# motherboard.net
KiCad netlist of a schematic drawn in EAGLE
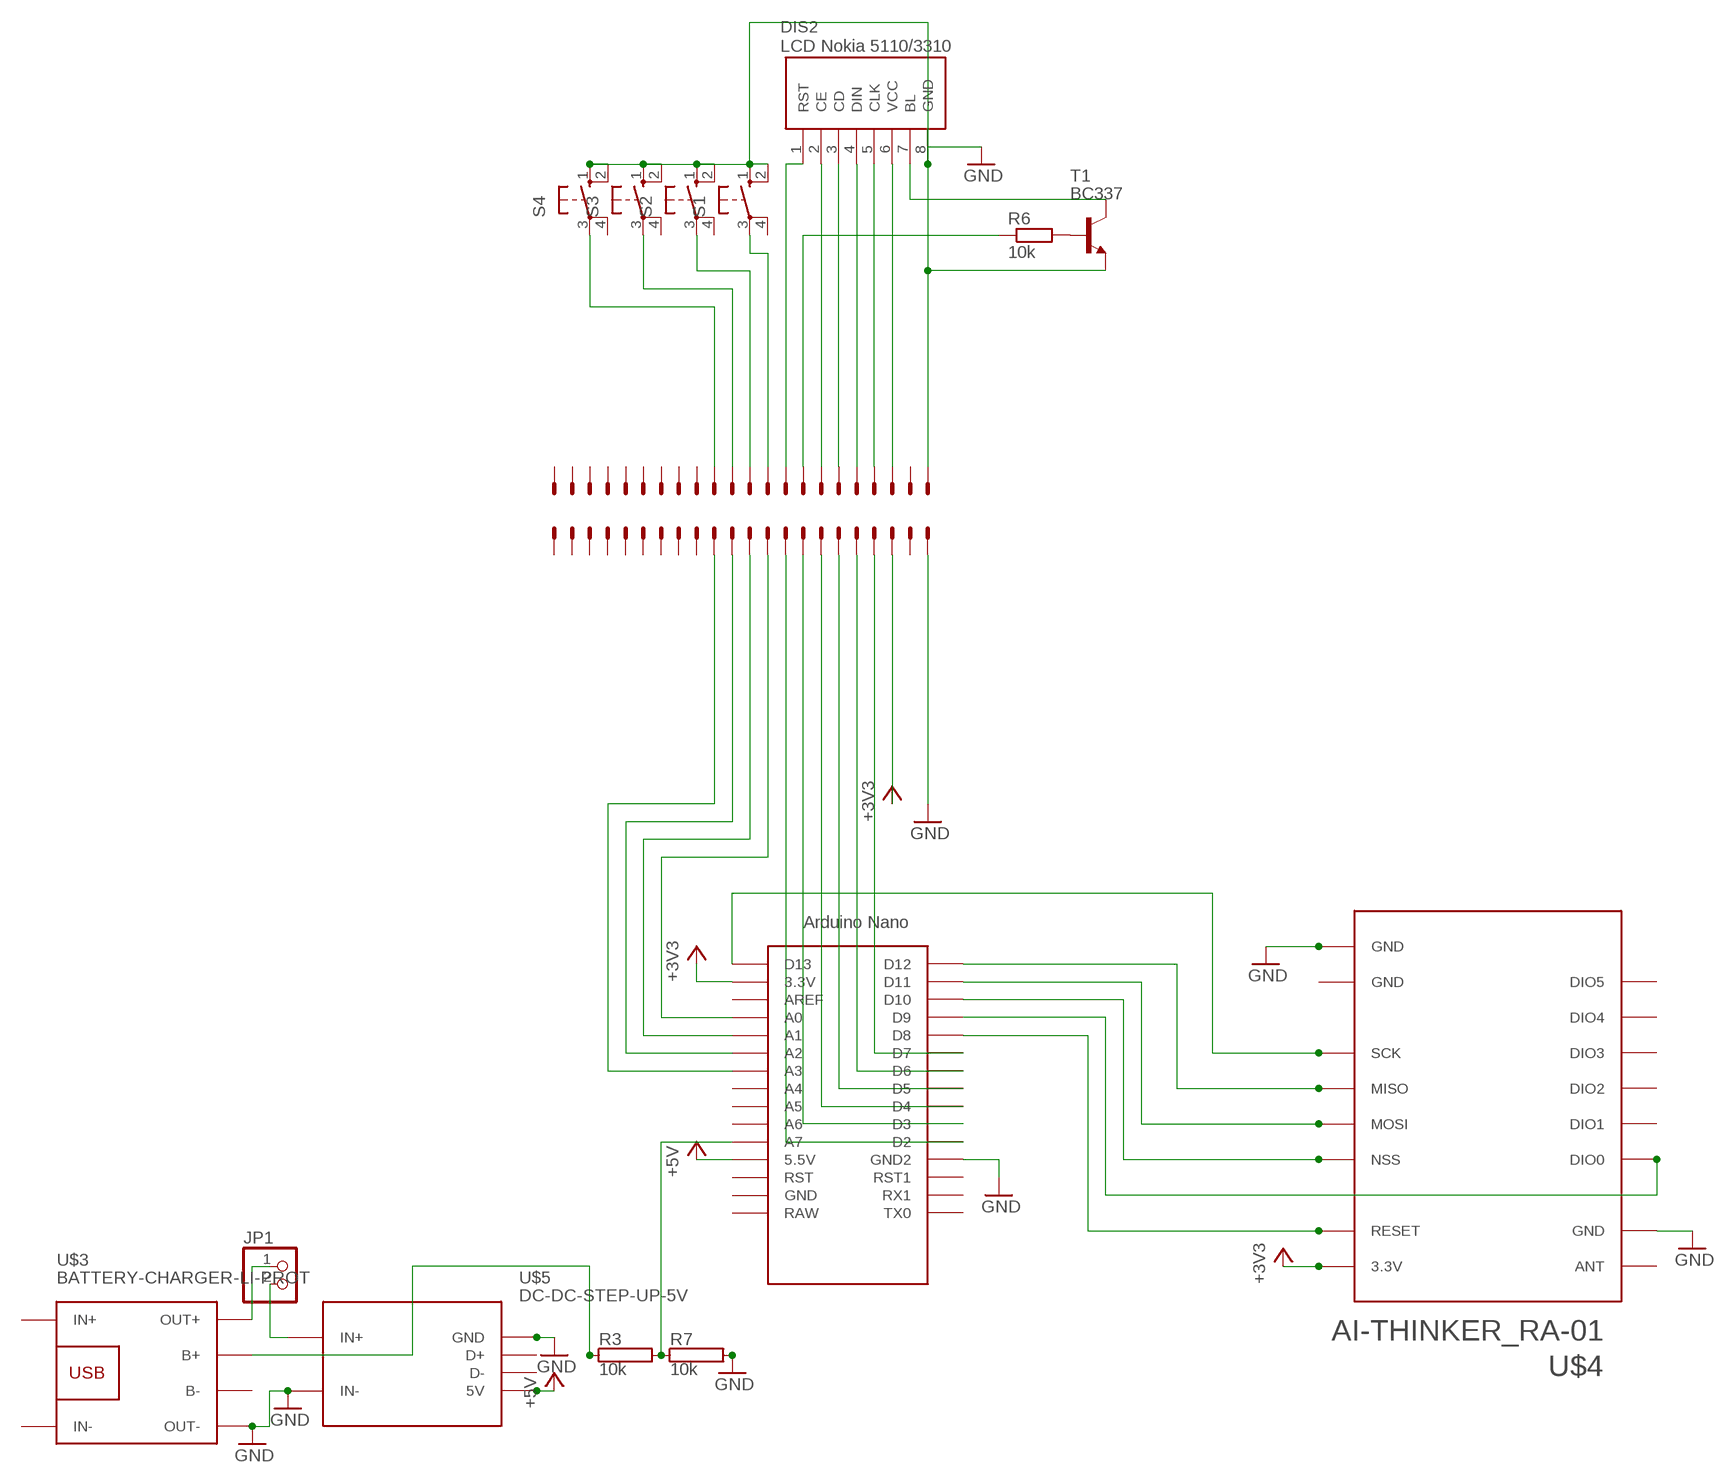
[diagram p0: schematic, sheet 1]

(export (version "E")
  (design (tool "Eeschema 10.0.6"))
  (components
    (comp (ref "DIS2")
      (value "NOKIA5110")
      (footprint "eagle-import:NOKIA5110")
      (libsource (lib "eagle-import") (part "NOKIA5110"))
    )
    (comp (ref "J1")
      (value "XF2L-2235-1")
      (footprint "eagle-import:XF2L-2235-1")
      (fields (field (name "MPN") "XF2L-2235-1A"))
      (libsource (lib "eagle-import") (part "XF2-22?35-1L"))
    )
    (comp (ref "J2")
      (value "XF2L-2235-1")
      (footprint "eagle-import:XF2L-2235-1")
      (fields (field (name "MPN") "XF2L-2235-1A"))
      (libsource (lib "eagle-import") (part "XF2-22?35-1L"))
    )
    (comp (ref "JP1")
      (value "PINHD-1X2/90")
      (footprint "eagle-import:1X02_90")
      (libsource (lib "eagle-import") (part "PINHD-1X2/90"))
    )
    (comp (ref "R3")
      (value "10k")
      (footprint "eagle-import:AC01")
      (libsource (lib "eagle-import") (part "RAC01"))
    )
    (comp (ref "R6")
      (value "10k")
      (footprint "eagle-import:0204_5")
      (libsource (lib "eagle-import") (part "R-EU_0204/5"))
    )
    (comp (ref "R7")
      (value "10k")
      (footprint "eagle-import:AC01")
      (libsource (lib "eagle-import") (part "RAC01"))
    )
    (comp (ref "S1")
      (value "10-XX")
      (footprint "eagle-import:B3F-10XX")
      (fields (field (name "MPN") "B3F-1000"))
      (libsource (lib "eagle-import") (part "10-XX"))
    )
    (comp (ref "S2")
      (value "10-XX")
      (footprint "eagle-import:B3F-10XX")
      (fields (field (name "MPN") "B3F-1000"))
      (libsource (lib "eagle-import") (part "10-XX"))
    )
    (comp (ref "S3")
      (value "10-XX")
      (footprint "eagle-import:B3F-10XX")
      (fields (field (name "MPN") "B3F-1000"))
      (libsource (lib "eagle-import") (part "10-XX"))
    )
    (comp (ref "S4")
      (value "10-XX")
      (footprint "eagle-import:B3F-10XX")
      (fields (field (name "MPN") "B3F-1000"))
      (libsource (lib "eagle-import") (part "10-XX"))
    )
    (comp (ref "T1")
      (value "BC337")
      (footprint "eagle-import:TO92")
      (libsource (lib "eagle-import") (part "BC337"))
    )
    (comp (ref "U$1")
      (value "NANO")
      (footprint "eagle-import:NANO")
      (libsource (lib "eagle-import") (part "NANO"))
    )
    (comp (ref "U$3")
      (value "BATTERY-CHARGER-LI-PROT")
      (footprint "eagle-import:BATTERY-CHARGER-LI-PROT")
      (libsource (lib "eagle-import") (part "BATTERY-CHARGER-LI-PROT"))
    )
    (comp (ref "U$4")
      (value "AI-THINKER_RA-01")
      (footprint "eagle-import:AI-THINKER_RA-01")
      (libsource (lib "eagle-import") (part "AI-THINKER_RA-01"))
    )
    (comp (ref "U$5")
      (value "DC-DC-STEP-UP-5V")
      (footprint "eagle-import:DC-DC-STEP-UP-5V")
      (libsource (lib "eagle-import") (part "DC-DC-STEP-UP-5V"))
    )
  )
  (nets
    (net (code "1") (name "+3V3") (class "Default")
      (node (ref "J1") (pin "20") (pinfunction "MS_20") (pintype "passive"))
      (node (ref "U$1") (pin "3.3V") (pinfunction "3.3V_3.3V") (pintype "bidirectional"))
      (node (ref "U$4") (pin "P$3") (pinfunction "3.3V_P$3") (pintype "bidirectional"))
    )
    (net (code "2") (name "+5V") (class "Default")
      (node (ref "U$1") (pin "5V") (pinfunction "5.5V_5V") (pintype "bidirectional"))
      (node (ref "U$5") (pin "5V") (pinfunction "5V_5V") (pintype "bidirectional"))
    )
    (net (code "3") (name "GND") (class "Default")
      (node (ref "DIS2") (pin "8") (pinfunction "GND_8") (pintype "power_in"))
      (node (ref "J1") (pin "22") (pinfunction "MS_22") (pintype "passive"))
      (node (ref "J2") (pin "1") (pinfunction "MSV_1") (pintype "passive"))
      (node (ref "R7") (pin "2") (pinfunction "2_2") (pintype "passive"))
      (node (ref "S1") (pin "1") (pinfunction "S_1") (pintype "passive"))
      (node (ref "S1") (pin "2") (pinfunction "S1_2") (pintype "passive"))
      (node (ref "S2") (pin "1") (pinfunction "S_1") (pintype "passive"))
      (node (ref "S2") (pin "2") (pinfunction "S1_2") (pintype "passive"))
      (node (ref "S3") (pin "1") (pinfunction "S_1") (pintype "passive"))
      (node (ref "S3") (pin "2") (pinfunction "S1_2") (pintype "passive"))
      (node (ref "S4") (pin "1") (pinfunction "S_1") (pintype "passive"))
      (node (ref "S4") (pin "2") (pinfunction "S1_2") (pintype "passive"))
      (node (ref "T1") (pin "1") (pinfunction "E_1") (pintype "passive"))
      (node (ref "U$1") (pin "GND1") (pinfunction "GND2_GND1") (pintype "bidirectional"))
      (node (ref "U$3") (pin "OUT-") (pinfunction "OUT-_OUT-") (pintype "bidirectional"))
      (node (ref "U$4") (pin "P$16") (pinfunction "GND_P$16") (pintype "bidirectional"))
      (node (ref "U$4") (pin "P$2") (pinfunction "GND_P$2") (pintype "bidirectional"))
      (node (ref "U$5") (pin "GND") (pinfunction "GND_GND") (pintype "bidirectional"))
      (node (ref "U$5") (pin "IN-") (pinfunction "IN-_IN-") (pintype "power_in"))
    )
    (net (code "4") (name "Net-(DIS2-BL)") (class "Default")
      (node (ref "DIS2") (pin "7") (pinfunction "BL_7") (pintype "bidirectional"))
      (node (ref "T1") (pin "3") (pinfunction "C_3") (pintype "passive"))
    )
    (net (code "5") (name "Net-(DIS2-CD)") (class "Default")
      (node (ref "DIS2") (pin "3") (pinfunction "CD_3") (pintype "bidirectional"))
      (node (ref "J2") (pin "6") (pinfunction "MS_6") (pintype "passive"))
    )
    (net (code "6") (name "Net-(DIS2-CE)") (class "Default")
      (node (ref "DIS2") (pin "2") (pinfunction "CE_2") (pintype "bidirectional"))
      (node (ref "J2") (pin "7") (pinfunction "MS_7") (pintype "passive"))
    )
    (net (code "7") (name "Net-(DIS2-CLK)") (class "Default")
      (node (ref "DIS2") (pin "5") (pinfunction "CLK_5") (pintype "bidirectional"))
      (node (ref "J2") (pin "4") (pinfunction "MS_4") (pintype "passive"))
    )
    (net (code "8") (name "Net-(DIS2-DIN)") (class "Default")
      (node (ref "DIS2") (pin "4") (pinfunction "DIN_4") (pintype "bidirectional"))
      (node (ref "J2") (pin "5") (pinfunction "MS_5") (pintype "passive"))
    )
    (net (code "9") (name "Net-(DIS2-RST)") (class "Default")
      (node (ref "DIS2") (pin "1") (pinfunction "RST_1") (pintype "bidirectional"))
      (node (ref "J2") (pin "9") (pinfunction "MS_9") (pintype "passive"))
    )
    (net (code "10") (name "Net-(DIS2-VCC)") (class "Default")
      (node (ref "DIS2") (pin "6") (pinfunction "VCC_6") (pintype "power_in"))
      (node (ref "J2") (pin "3") (pinfunction "MS_3") (pintype "passive"))
    )
    (net (code "11") (name "Net-(J1B-MS)") (class "Default")
      (node (ref "J1") (pin "10") (pinfunction "MS_10") (pintype "passive"))
      (node (ref "U$1") (pin "A3") (pinfunction "A3_A3") (pintype "bidirectional"))
    )
    (net (code "12") (name "Net-(J1C-MS)") (class "Default")
      (node (ref "J1") (pin "11") (pinfunction "MS_11") (pintype "passive"))
      (node (ref "U$1") (pin "A2") (pinfunction "A2_A2") (pintype "bidirectional"))
    )
    (net (code "13") (name "Net-(J1D-MS)") (class "Default")
      (node (ref "J1") (pin "12") (pinfunction "MS_12") (pintype "passive"))
      (node (ref "U$1") (pin "A1") (pinfunction "A1_A1") (pintype "bidirectional"))
    )
    (net (code "14") (name "Net-(J1E-MS)") (class "Default")
      (node (ref "J1") (pin "13") (pinfunction "MS_13") (pintype "passive"))
      (node (ref "U$1") (pin "A0") (pinfunction "A0_A0") (pintype "bidirectional"))
    )
    (net (code "15") (name "Net-(J1F-MS)") (class "Default")
      (node (ref "J1") (pin "14") (pinfunction "MS_14") (pintype "passive"))
      (node (ref "U$1") (pin "D2") (pinfunction "D2_D2") (pintype "bidirectional"))
    )
    (net (code "16") (name "Net-(J1G-MS)") (class "Default")
      (node (ref "J1") (pin "15") (pinfunction "MS_15") (pintype "passive"))
      (node (ref "U$1") (pin "D3") (pinfunction "D3_D3") (pintype "bidirectional"))
    )
    (net (code "17") (name "Net-(J1H-MS)") (class "Default")
      (node (ref "J1") (pin "16") (pinfunction "MS_16") (pintype "passive"))
      (node (ref "U$1") (pin "D4") (pinfunction "D4_D4") (pintype "bidirectional"))
    )
    (net (code "18") (name "Net-(J1I-MS)") (class "Default")
      (node (ref "J1") (pin "17") (pinfunction "MS_17") (pintype "passive"))
      (node (ref "U$1") (pin "D5") (pinfunction "D5_D5") (pintype "bidirectional"))
    )
    (net (code "19") (name "Net-(J1J-MS)") (class "Default")
      (node (ref "J1") (pin "18") (pinfunction "MS_18") (pintype "passive"))
      (node (ref "U$1") (pin "D6") (pinfunction "D6_D6") (pintype "bidirectional"))
    )
    (net (code "20") (name "Net-(J1K-MS)") (class "Default")
      (node (ref "J1") (pin "19") (pinfunction "MS_19") (pintype "passive"))
      (node (ref "U$1") (pin "D7") (pinfunction "D7_D7") (pintype "bidirectional"))
    )
    (net (code "21") (name "Net-(J2B-MS)") (class "Default")
      (node (ref "J2") (pin "10") (pinfunction "MS_10") (pintype "passive"))
      (node (ref "S1") (pin "3") (pinfunction "P_3") (pintype "passive"))
    )
    (net (code "22") (name "Net-(J2C-MS)") (class "Default")
      (node (ref "J2") (pin "11") (pinfunction "MS_11") (pintype "passive"))
      (node (ref "S2") (pin "3") (pinfunction "P_3") (pintype "passive"))
    )
    (net (code "23") (name "Net-(J2D-MS)") (class "Default")
      (node (ref "J2") (pin "12") (pinfunction "MS_12") (pintype "passive"))
      (node (ref "S3") (pin "3") (pinfunction "P_3") (pintype "passive"))
    )
    (net (code "24") (name "Net-(J2E-MS)") (class "Default")
      (node (ref "J2") (pin "13") (pinfunction "MS_13") (pintype "passive"))
      (node (ref "S4") (pin "3") (pinfunction "P_3") (pintype "passive"))
    )
    (net (code "25") (name "Net-(J2U-MS)") (class "Default")
      (node (ref "J2") (pin "8") (pinfunction "MS_8") (pintype "passive"))
      (node (ref "R6") (pin "1") (pinfunction "1_1") (pintype "passive"))
    )
    (net (code "26") (name "Net-(JP1-Pad1)") (class "Default")
      (node (ref "JP1") (pin "1") (pinfunction "1_1") (pintype "passive"))
      (node (ref "U$3") (pin "OUT+") (pinfunction "OUT+_OUT+") (pintype "bidirectional"))
    )
    (net (code "27") (name "Net-(JP1-Pad2)") (class "Default")
      (node (ref "JP1") (pin "2") (pinfunction "2_2") (pintype "passive"))
      (node (ref "U$5") (pin "IN+") (pinfunction "IN+_IN+") (pintype "power_in"))
    )
    (net (code "28") (name "Net-(R3-Pad1)") (class "Default")
      (node (ref "R3") (pin "1") (pinfunction "1_1") (pintype "passive"))
      (node (ref "U$3") (pin "B+") (pinfunction "B+_B+") (pintype "bidirectional"))
    )
    (net (code "29") (name "Net-(R3-Pad2)") (class "Default")
      (node (ref "R3") (pin "2") (pinfunction "2_2") (pintype "passive"))
      (node (ref "R7") (pin "1") (pinfunction "1_1") (pintype "passive"))
      (node (ref "U$1") (pin "A7") (pinfunction "A7_A7") (pintype "bidirectional"))
    )
    (net (code "30") (name "Net-(T1-B)") (class "Default")
      (node (ref "R6") (pin "2") (pinfunction "2_2") (pintype "passive"))
      (node (ref "T1") (pin "2") (pinfunction "B_2") (pintype "passive"))
    )
    (net (code "31") (name "Net-(U$4-DIO0)") (class "Default")
      (node (ref "U$1") (pin "D9") (pinfunction "D9_D9") (pintype "bidirectional"))
      (node (ref "U$4") (pin "P$5") (pinfunction "DIO0_P$5") (pintype "bidirectional"))
    )
    (net (code "32") (name "Net-(U$4-MISO)") (class "Default")
      (node (ref "U$1") (pin "D12") (pinfunction "D12_D12") (pintype "bidirectional"))
      (node (ref "U$4") (pin "P$13") (pinfunction "MISO_P$13") (pintype "bidirectional"))
    )
    (net (code "33") (name "Net-(U$4-MOSI)") (class "Default")
      (node (ref "U$1") (pin "D11") (pinfunction "D11_D11") (pintype "bidirectional"))
      (node (ref "U$4") (pin "P$14") (pinfunction "MOSI_P$14") (pintype "bidirectional"))
    )
    (net (code "34") (name "Net-(U$4-NSS)") (class "Default")
      (node (ref "U$1") (pin "D10") (pinfunction "D10_D10") (pintype "bidirectional"))
      (node (ref "U$4") (pin "P$15") (pinfunction "NSS_P$15") (pintype "bidirectional"))
    )
    (net (code "35") (name "Net-(U$4-RESET)") (class "Default")
      (node (ref "U$1") (pin "D8") (pinfunction "D8_D8") (pintype "bidirectional"))
      (node (ref "U$4") (pin "P$4") (pinfunction "RESET_P$4") (pintype "bidirectional"))
    )
    (net (code "36") (name "Net-(U$4-SCK)") (class "Default")
      (node (ref "U$1") (pin "D13") (pinfunction "D13_D13") (pintype "bidirectional"))
      (node (ref "U$4") (pin "P$12") (pinfunction "SCK_P$12") (pintype "bidirectional"))
    )
    (net (code "37") (name "unconnected-(J1A-MSV-Pad1)") (class "Default")
      (node (ref "J1") (pin "1") (pinfunction "MSV_1") (pintype "passive"))
    )
    (net (code "38") (name "unconnected-(J1L-MS-Pad2)") (class "Default")
      (node (ref "J1") (pin "2") (pinfunction "MS_2") (pintype "passive"))
    )
    (net (code "39") (name "unconnected-(J1N-MS-Pad21)") (class "Default")
      (node (ref "J1") (pin "21") (pinfunction "MS_21") (pintype "passive"))
    )
    (net (code "40") (name "unconnected-(J1P-MS-Pad3)") (class "Default")
      (node (ref "J1") (pin "3") (pinfunction "MS_3") (pintype "passive"))
    )
    (net (code "41") (name "unconnected-(J1Q-MS-Pad4)") (class "Default")
      (node (ref "J1") (pin "4") (pinfunction "MS_4") (pintype "passive"))
    )
    (net (code "42") (name "unconnected-(J1R-MS-Pad5)") (class "Default")
      (node (ref "J1") (pin "5") (pinfunction "MS_5") (pintype "passive"))
    )
    (net (code "43") (name "unconnected-(J1S-MS-Pad6)") (class "Default")
      (node (ref "J1") (pin "6") (pinfunction "MS_6") (pintype "passive"))
    )
    (net (code "44") (name "unconnected-(J1T-MS-Pad7)") (class "Default")
      (node (ref "J1") (pin "7") (pinfunction "MS_7") (pintype "passive"))
    )
    (net (code "45") (name "unconnected-(J1U-MS-Pad8)") (class "Default")
      (node (ref "J1") (pin "8") (pinfunction "MS_8") (pintype "passive"))
    )
    (net (code "46") (name "unconnected-(J1V-MS-Pad9)") (class "Default")
      (node (ref "J1") (pin "9") (pinfunction "MS_9") (pintype "passive"))
    )
    (net (code "47") (name "unconnected-(J2F-MS-Pad14)") (class "Default")
      (node (ref "J2") (pin "14") (pinfunction "MS_14") (pintype "passive"))
    )
    (net (code "48") (name "unconnected-(J2G-MS-Pad15)") (class "Default")
      (node (ref "J2") (pin "15") (pinfunction "MS_15") (pintype "passive"))
    )
    (net (code "49") (name "unconnected-(J2H-MS-Pad16)") (class "Default")
      (node (ref "J2") (pin "16") (pinfunction "MS_16") (pintype "passive"))
    )
    (net (code "50") (name "unconnected-(J2I-MS-Pad17)") (class "Default")
      (node (ref "J2") (pin "17") (pinfunction "MS_17") (pintype "passive"))
    )
    (net (code "51") (name "unconnected-(J2J-MS-Pad18)") (class "Default")
      (node (ref "J2") (pin "18") (pinfunction "MS_18") (pintype "passive"))
    )
    (net (code "52") (name "unconnected-(J2K-MS-Pad19)") (class "Default")
      (node (ref "J2") (pin "19") (pinfunction "MS_19") (pintype "passive"))
    )
    (net (code "53") (name "unconnected-(J2L-MS-Pad2)") (class "Default")
      (node (ref "J2") (pin "2") (pinfunction "MS_2") (pintype "passive"))
    )
    (net (code "54") (name "unconnected-(J2M-MS-Pad20)") (class "Default")
      (node (ref "J2") (pin "20") (pinfunction "MS_20") (pintype "passive"))
    )
    (net (code "55") (name "unconnected-(J2N-MS-Pad21)") (class "Default")
      (node (ref "J2") (pin "21") (pinfunction "MS_21") (pintype "passive"))
    )
    (net (code "56") (name "unconnected-(J2O-MS-Pad22)") (class "Default")
      (node (ref "J2") (pin "22") (pinfunction "MS_22") (pintype "passive"))
    )
    (net (code "57") (name "unconnected-(S1-P1-Pad4)") (class "Default")
      (node (ref "S1") (pin "4") (pinfunction "P1_4") (pintype "passive"))
    )
    (net (code "58") (name "unconnected-(S2-P1-Pad4)") (class "Default")
      (node (ref "S2") (pin "4") (pinfunction "P1_4") (pintype "passive"))
    )
    (net (code "59") (name "unconnected-(S3-P1-Pad4)") (class "Default")
      (node (ref "S3") (pin "4") (pinfunction "P1_4") (pintype "passive"))
    )
    (net (code "60") (name "unconnected-(S4-P1-Pad4)") (class "Default")
      (node (ref "S4") (pin "4") (pinfunction "P1_4") (pintype "passive"))
    )
    (net (code "61") (name "unconnected-(U$1-PadA4)") (class "Default")
      (node (ref "U$1") (pin "A4") (pinfunction "A4_A4") (pintype "bidirectional"))
    )
    (net (code "62") (name "unconnected-(U$1-PadA5)") (class "Default")
      (node (ref "U$1") (pin "A5") (pinfunction "A5_A5") (pintype "bidirectional"))
    )
    (net (code "63") (name "unconnected-(U$1-PadA6)") (class "Default")
      (node (ref "U$1") (pin "A6") (pinfunction "A6_A6") (pintype "bidirectional"))
    )
    (net (code "64") (name "unconnected-(U$1-PadAREF)") (class "Default")
      (node (ref "U$1") (pin "AREF") (pinfunction "AREF_AREF") (pintype "bidirectional"))
    )
    (net (code "65") (name "unconnected-(U$1-PadGND)") (class "Default")
      (node (ref "U$1") (pin "GND") (pinfunction "GND_GND") (pintype "bidirectional"))
    )
    (net (code "66") (name "unconnected-(U$1-PadRAW)") (class "Default")
      (node (ref "U$1") (pin "RAW") (pinfunction "RAW_RAW") (pintype "bidirectional"))
    )
    (net (code "67") (name "unconnected-(U$1-PadRST)") (class "Default")
      (node (ref "U$1") (pin "RST") (pinfunction "RST_RST") (pintype "bidirectional"))
    )
    (net (code "68") (name "unconnected-(U$1-PadRST1)") (class "Default")
      (node (ref "U$1") (pin "RST1") (pinfunction "RST1_RST1") (pintype "bidirectional"))
    )
    (net (code "69") (name "unconnected-(U$1-PadRX1)") (class "Default")
      (node (ref "U$1") (pin "RX1") (pinfunction "RX1_RX1") (pintype "bidirectional"))
    )
    (net (code "70") (name "unconnected-(U$1-PadTX0)") (class "Default")
      (node (ref "U$1") (pin "TX0") (pinfunction "TX0_TX0") (pintype "bidirectional"))
    )
    (net (code "71") (name "unconnected-(U$3-PadB-)") (class "Default")
      (node (ref "U$3") (pin "B-") (pinfunction "B-_B-") (pintype "bidirectional"))
    )
    (net (code "72") (name "unconnected-(U$3-PadIN+)") (class "Default")
      (node (ref "U$3") (pin "IN+") (pinfunction "IN+_IN+") (pintype "bidirectional"))
    )
    (net (code "73") (name "unconnected-(U$3-PadIN-)") (class "Default")
      (node (ref "U$3") (pin "IN-") (pinfunction "IN-_IN-") (pintype "bidirectional"))
    )
    (net (code "74") (name "unconnected-(U$4-ANT-PadP$1)") (class "Default")
      (node (ref "U$4") (pin "P$1") (pinfunction "ANT_P$1") (pintype "bidirectional"))
    )
    (net (code "75") (name "unconnected-(U$4-DIO1-PadP$6)") (class "Default")
      (node (ref "U$4") (pin "P$6") (pinfunction "DIO1_P$6") (pintype "bidirectional"))
    )
    (net (code "76") (name "unconnected-(U$4-DIO2-PadP$7)") (class "Default")
      (node (ref "U$4") (pin "P$7") (pinfunction "DIO2_P$7") (pintype "bidirectional"))
    )
    (net (code "77") (name "unconnected-(U$4-DIO3-PadP$8)") (class "Default")
      (node (ref "U$4") (pin "P$8") (pinfunction "DIO3_P$8") (pintype "bidirectional"))
    )
    (net (code "78") (name "unconnected-(U$4-DIO4-PadP$10)") (class "Default")
      (node (ref "U$4") (pin "P$10") (pinfunction "DIO4_P$10") (pintype "bidirectional"))
    )
    (net (code "79") (name "unconnected-(U$4-DIO5-PadP$11)") (class "Default")
      (node (ref "U$4") (pin "P$11") (pinfunction "DIO5_P$11") (pintype "bidirectional"))
    )
    (net (code "80") (name "unconnected-(U$4-GND-PadP$9)") (class "Default")
      (node (ref "U$4") (pin "P$9") (pinfunction "GND_P$9") (pintype "bidirectional"))
    )
    (net (code "81") (name "unconnected-(U$5-PadD+)") (class "Default")
      (node (ref "U$5") (pin "D+") (pinfunction "D+_D+") (pintype "bidirectional"))
    )
    (net (code "82") (name "unconnected-(U$5-PadD-)") (class "Default")
      (node (ref "U$5") (pin "D-") (pinfunction "D-_D-") (pintype "bidirectional"))
    )
  )
)
